# audio.net
KiCad netlist of a schematic drawn in Altium Designer
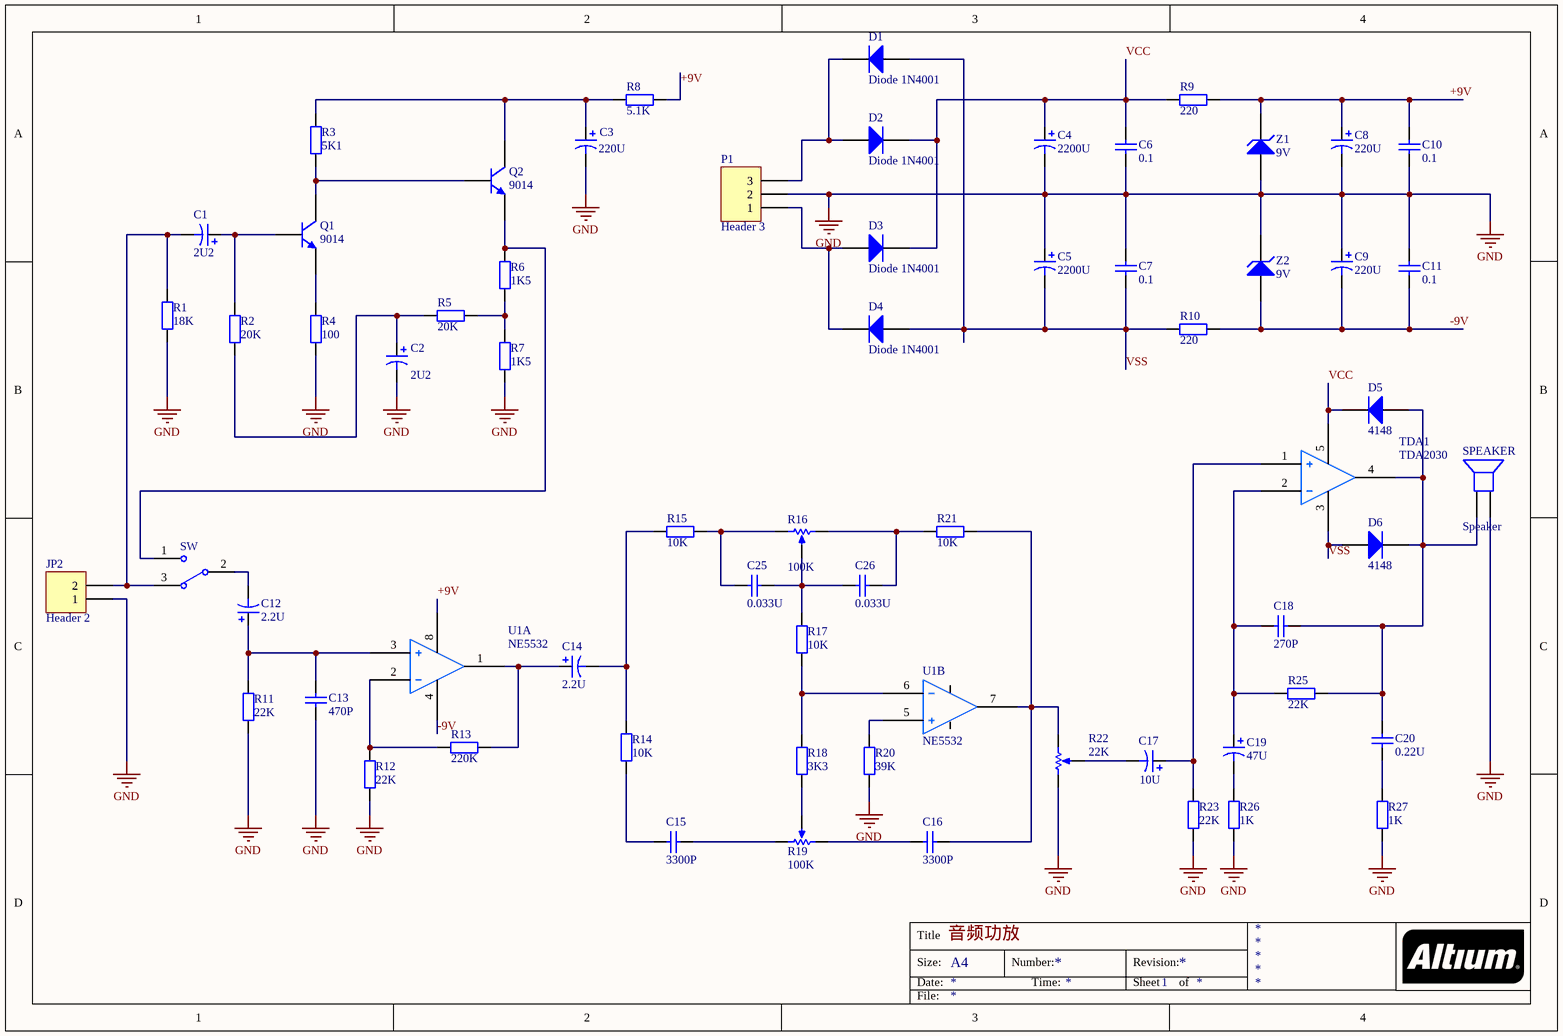
[diagram p0: audio.SchDoc]

(export (version "E")
  (design (tool "Eeschema 10.0.6"))
  (components
    (comp (ref "C1")
      (value "2U2")
      (footprint "CD0.2")
      (description "Polarized Capacitor (Radial)")
      (fields (field (name "PUBLISHER") "Altium Limited"))
      (libsource (lib "音频功放") (part "Cap Pol1"))
    )
    (comp (ref "C2")
      (value "2U2")
      (footprint "CD0.2")
      (description "Polarized Capacitor (Radial)")
      (fields (field (name "PUBLISHER") "Altium Limited"))
      (libsource (lib "音频功放") (part "Cap Pol1"))
    )
    (comp (ref "C3")
      (value "220U")
      (footprint "CD0.2")
      (description "Polarized Capacitor (Radial)")
      (fields (field (name "PUBLISHER") "Altium Limited"))
      (libsource (lib "音频功放") (part "Cap Pol1"))
    )
    (comp (ref "C4")
      (value "2200U")
      (footprint "CD0.2")
      (description "Polarized Capacitor (Radial)")
      (fields (field (name "PUBLISHER") "Altium Limited"))
      (libsource (lib "音频功放") (part "Cap Pol1"))
    )
    (comp (ref "C5")
      (value "2200U")
      (footprint "CD0.2")
      (description "Polarized Capacitor (Radial)")
      (fields (field (name "PUBLISHER") "Altium Limited"))
      (libsource (lib "音频功放") (part "Cap Pol1"))
    )
    (comp (ref "C6")
      (value "0.1")
      (footprint "C0.2A")
      (description "Capacitor")
      (fields (field (name "PUBLISHER") "Altium Limited"))
      (libsource (lib "音频功放") (part "Cap"))
    )
    (comp (ref "C7")
      (value "0.1")
      (footprint "C0.2A")
      (description "Capacitor")
      (fields (field (name "PUBLISHER") "Altium Limited"))
      (libsource (lib "音频功放") (part "Cap"))
    )
    (comp (ref "C8")
      (value "220U")
      (footprint "CD0.2")
      (description "Polarized Capacitor (Radial)")
      (fields (field (name "PUBLISHER") "Altium Limited"))
      (libsource (lib "音频功放") (part "Cap Pol1"))
    )
    (comp (ref "C9")
      (value "220U")
      (footprint "CD0.2")
      (description "Polarized Capacitor (Radial)")
      (fields (field (name "PUBLISHER") "Altium Limited"))
      (libsource (lib "音频功放") (part "Cap Pol1"))
    )
    (comp (ref "C10")
      (value "0.1")
      (footprint "C0.2A")
      (description "Capacitor")
      (fields (field (name "PUBLISHER") "Altium Limited"))
      (libsource (lib "音频功放") (part "Cap"))
    )
    (comp (ref "C11")
      (value "0.1")
      (footprint "C0.2A")
      (description "Capacitor")
      (fields (field (name "PUBLISHER") "Altium Limited"))
      (libsource (lib "音频功放") (part "Cap"))
    )
    (comp (ref "C12")
      (value "2.2U")
      (footprint "CD0.2")
      (description "Polarized Capacitor (Radial)")
      (fields (field (name "PUBLISHER") "Altium Limited"))
      (libsource (lib "音频功放") (part "Cap Pol1"))
    )
    (comp (ref "C13")
      (value "470P")
      (footprint "C0.2A")
      (description "Capacitor")
      (fields (field (name "PUBLISHER") "Altium Limited"))
      (libsource (lib "音频功放") (part "Cap"))
    )
    (comp (ref "C14")
      (value "2.2U")
      (footprint "CD0.2")
      (description "Polarized Capacitor (Radial)")
      (fields (field (name "PUBLISHER") "Altium Limited"))
      (libsource (lib "音频功放") (part "Cap Pol1"))
    )
    (comp (ref "C15")
      (value "3300P")
      (footprint "C0.2A")
      (description "Capacitor")
      (fields (field (name "PUBLISHER") "Altium Limited"))
      (libsource (lib "音频功放") (part "Cap"))
    )
    (comp (ref "C16")
      (value "3300P")
      (footprint "C0.2A")
      (description "Capacitor")
      (fields (field (name "PUBLISHER") "Altium Limited"))
      (libsource (lib "音频功放") (part "Cap"))
    )
    (comp (ref "C17")
      (value "10U")
      (footprint "CD0.2")
      (description "Polarized Capacitor (Radial)")
      (fields (field (name "PUBLISHER") "Altium Limited"))
      (libsource (lib "音频功放") (part "Cap Pol1"))
    )
    (comp (ref "C18")
      (value "270P")
      (footprint "C0.2A")
      (description "Capacitor")
      (fields (field (name "PUBLISHER") "Altium Limited"))
      (libsource (lib "音频功放") (part "Cap"))
    )
    (comp (ref "C19")
      (value "47U")
      (footprint "CD0.2")
      (description "Polarized Capacitor (Radial)")
      (fields (field (name "PUBLISHER") "Altium Limited"))
      (libsource (lib "音频功放") (part "Cap Pol1"))
    )
    (comp (ref "C20")
      (value "0.22U")
      (footprint "C0.2A")
      (description "Capacitor")
      (fields (field (name "PUBLISHER") "Altium Limited"))
      (libsource (lib "音频功放") (part "Cap"))
    )
    (comp (ref "C25")
      (value "0.033U")
      (footprint "C0.2A")
      (description "Capacitor")
      (fields (field (name "PUBLISHER") "Altium Limited"))
      (libsource (lib "音频功放") (part "Cap"))
    )
    (comp (ref "C26")
      (value "0.033U")
      (footprint "C0.2A")
      (description "Capacitor")
      (fields (field (name "PUBLISHER") "Altium Limited"))
      (libsource (lib "音频功放") (part "Cap"))
    )
    (comp (ref "D1")
      (value "Diode 1N4001")
      (footprint "DIODE0.4")
      (description "1 Amp General Purpose Rectifier")
      (fields (field (name "PUBLISHER") "Altium Limited"))
      (libsource (lib "音频功放") (part "Diode 1N4001"))
    )
    (comp (ref "D2")
      (value "Diode 1N4001")
      (footprint "DIODE0.4")
      (description "1 Amp General Purpose Rectifier")
      (fields (field (name "PUBLISHER") "Altium Limited"))
      (libsource (lib "音频功放") (part "Diode 1N4001"))
    )
    (comp (ref "D3")
      (value "Diode 1N4001")
      (footprint "DIODE0.4")
      (description "1 Amp General Purpose Rectifier")
      (fields (field (name "PUBLISHER") "Altium Limited"))
      (libsource (lib "音频功放") (part "Diode 1N4001"))
    )
    (comp (ref "D4")
      (value "Diode 1N4001")
      (footprint "DIODE0.4")
      (description "1 Amp General Purpose Rectifier")
      (fields (field (name "PUBLISHER") "Altium Limited"))
      (libsource (lib "音频功放") (part "Diode 1N4001"))
    )
    (comp (ref "D5")
      (value "4148")
      (footprint "DIODE0.4")
      (description "High Conductance Fast Diode")
      (fields (field (name "PUBLISHER") "Altium Limited"))
      (libsource (lib "音频功放") (part "Diode 1N4148"))
    )
    (comp (ref "D6")
      (value "4148")
      (footprint "DIODE0.4")
      (description "High Conductance Fast Diode")
      (fields (field (name "PUBLISHER") "Altium Limited"))
      (libsource (lib "音频功放") (part "Diode 1N4148"))
    )
    (comp (ref "JP2")
      (value "Header 2")
      (footprint "p2")
      (description "Header, 2-Pin")
      (fields (field (name "PUBLISHER") "Altium Limited"))
      (libsource (lib "音频功放") (part "Header 2"))
    )
    (comp (ref "P1")
      (value "Header 3")
      (footprint "p3")
      (description "Header, 3-Pin")
      (fields (field (name "PUBLISHER") "Altium Limited"))
      (libsource (lib "音频功放") (part "Header 3"))
    )
    (comp (ref "Q1")
      (value "9014")
      (footprint "TO-226-AA")
      (description "NPN General Purpose Amplifier")
      (fields (field (name "PUBLISHER") "Altium Limited"))
      (libsource (lib "音频功放") (part "2N3904"))
    )
    (comp (ref "Q2")
      (value "9014")
      (footprint "TO-226-AA")
      (description "NPN General Purpose Amplifier")
      (fields (field (name "PUBLISHER") "Altium Limited"))
      (libsource (lib "音频功放") (part "2N3904"))
    )
    (comp (ref "R1")
      (value "18K")
      (footprint "AXIAL-0.4")
      (description "Resistor")
      (fields (field (name "PUBLISHER") "Altium Limited"))
      (libsource (lib "音频功放") (part "Res2"))
    )
    (comp (ref "R2")
      (value "20K")
      (footprint "AXIAL-0.4")
      (description "Resistor")
      (fields (field (name "PUBLISHER") "Altium Limited"))
      (libsource (lib "音频功放") (part "Res2"))
    )
    (comp (ref "R3")
      (value "5K1")
      (footprint "AXIAL-0.4")
      (description "Resistor")
      (fields (field (name "PUBLISHER") "Altium Limited"))
      (libsource (lib "音频功放") (part "Res2"))
    )
    (comp (ref "R4")
      (value "100")
      (footprint "AXIAL-0.4")
      (description "Resistor")
      (fields (field (name "PUBLISHER") "Altium Limited"))
      (libsource (lib "音频功放") (part "Res2"))
    )
    (comp (ref "R5")
      (value "20K")
      (footprint "AXIAL-0.4")
      (description "Resistor")
      (fields (field (name "PUBLISHER") "Altium Limited"))
      (libsource (lib "") (part "Res2_1"))
    )
    (comp (ref "R6")
      (value "1K5")
      (footprint "AXIAL-0.4")
      (description "Resistor")
      (fields (field (name "PUBLISHER") "Altium Limited"))
      (libsource (lib "音频功放") (part "Res2"))
    )
    (comp (ref "R7")
      (value "1K5")
      (footprint "AXIAL-0.4")
      (description "Resistor")
      (fields (field (name "PUBLISHER") "Altium Limited"))
      (libsource (lib "音频功放") (part "Res2"))
    )
    (comp (ref "R8")
      (value "5.1K")
      (footprint "AXIAL-0.4")
      (description "Resistor")
      (fields (field (name "PUBLISHER") "Altium Limited"))
      (libsource (lib "") (part "Res2_1"))
    )
    (comp (ref "R9")
      (value "220")
      (footprint "AXIAL-0.4")
      (description "Resistor")
      (fields (field (name "PUBLISHER") "Altium Limited"))
      (libsource (lib "") (part "Res2_1"))
    )
    (comp (ref "R10")
      (value "220")
      (footprint "AXIAL-0.4")
      (description "Resistor")
      (fields (field (name "PUBLISHER") "Altium Limited"))
      (libsource (lib "") (part "Res2_1"))
    )
    (comp (ref "R11")
      (value "22K")
      (footprint "AXIAL-0.4")
      (description "Resistor")
      (fields (field (name "PUBLISHER") "Altium Limited"))
      (libsource (lib "音频功放") (part "Res2"))
    )
    (comp (ref "R12")
      (value "22K")
      (footprint "AXIAL-0.4")
      (description "Resistor")
      (fields (field (name "PUBLISHER") "Altium Limited"))
      (libsource (lib "音频功放") (part "Res2"))
    )
    (comp (ref "R13")
      (value "220K")
      (footprint "AXIAL-0.4")
      (description "Resistor")
      (fields (field (name "PUBLISHER") "Altium Limited"))
      (libsource (lib "") (part "Res2_1"))
    )
    (comp (ref "R14")
      (value "10K")
      (footprint "AXIAL-0.4")
      (description "Resistor")
      (fields (field (name "PUBLISHER") "Altium Limited"))
      (libsource (lib "音频功放") (part "Res2"))
    )
    (comp (ref "R15")
      (value "10K")
      (footprint "AXIAL-0.4")
      (description "Resistor")
      (fields (field (name "PUBLISHER") "Altium Limited"))
      (libsource (lib "") (part "Res2_1"))
    )
    (comp (ref "R16")
      (value "100K")
      (footprint "LK01")
      (description "Potentiometer")
      (fields (field (name "PUBLISHER") "Altium Limited"))
      (libsource (lib "音频功放") (part "RPot"))
    )
    (comp (ref "R17")
      (value "10K")
      (footprint "AXIAL-0.4")
      (description "Resistor")
      (fields (field (name "PUBLISHER") "Altium Limited"))
      (libsource (lib "音频功放") (part "Res2"))
    )
    (comp (ref "R18")
      (value "3K3")
      (footprint "AXIAL-0.4")
      (description "Resistor")
      (fields (field (name "PUBLISHER") "Altium Limited"))
      (libsource (lib "音频功放") (part "Res2"))
    )
    (comp (ref "R19")
      (value "100K")
      (footprint "LK01")
      (description "Potentiometer")
      (fields (field (name "PUBLISHER") "Altium Limited"))
      (libsource (lib "音频功放") (part "RPot"))
    )
    (comp (ref "R20")
      (value "39K")
      (footprint "AXIAL-0.4")
      (description "Resistor")
      (fields (field (name "PUBLISHER") "Altium Limited"))
      (libsource (lib "音频功放") (part "Res2"))
    )
    (comp (ref "R21")
      (value "10K")
      (footprint "AXIAL-0.4")
      (description "Resistor")
      (fields (field (name "PUBLISHER") "Altium Limited"))
      (libsource (lib "") (part "Res2_1"))
    )
    (comp (ref "R22")
      (value "22K")
      (footprint "LK01")
      (description "Potentiometer")
      (fields (field (name "PUBLISHER") "Altium Limited"))
      (libsource (lib "音频功放") (part "RPot"))
    )
    (comp (ref "R23")
      (value "22K")
      (footprint "AXIAL-0.4")
      (description "Resistor")
      (fields (field (name "PUBLISHER") "Altium Limited"))
      (libsource (lib "音频功放") (part "Res2"))
    )
    (comp (ref "R25")
      (value "22K")
      (footprint "AXIAL-0.4")
      (description "Resistor")
      (fields (field (name "PUBLISHER") "Altium Limited"))
      (libsource (lib "") (part "Res2_1"))
    )
    (comp (ref "R26")
      (value "1K")
      (footprint "AXIAL-0.4")
      (description "Resistor")
      (fields (field (name "PUBLISHER") "Altium Limited"))
      (libsource (lib "音频功放") (part "Res2"))
    )
    (comp (ref "R27")
      (value "1K")
      (footprint "AXIAL-0.4")
      (description "Resistor")
      (fields (field (name "PUBLISHER") "Altium Limited"))
      (libsource (lib "音频功放") (part "Res2"))
    )
    (comp (ref "SPEAKER")
      (value "Speaker")
      (footprint "p2")
      (description "Loudspeaker")
      (fields (field (name "PUBLISHER") "Altium Limited"))
      (libsource (lib "音频功放") (part "Speaker"))
    )
    (comp (ref "SW")
      (value "SW-SPDT")
      (footprint "SW")
      (description "SPDT Subminiature Toggle Switch, Right Angle Mounting, Vertical Actuation")
      (fields (field (name "PUBLISHER") "Altium Limited"))
      (libsource (lib "音频功放") (part "SW-SPDT"))
    )
    (comp (ref "TDA1") (value "TDA2030") (footprint "7805E") (libsource (lib "音频功放") (part "TDA2030")))
    (comp (ref "U1") (value "NE5532") (footprint "DIP8") (libsource (lib "音频功放") (part "NE5532")))
    (comp (ref "Z1")
      (value "9V")
      (footprint "DIODE0.4")
      (description "Zener Diode")
      (fields (field (name "PUBLISHER") "Altium Limited"))
      (libsource (lib "音频功放") (part "D Zener"))
    )
    (comp (ref "Z2")
      (value "9V")
      (footprint "DIODE0.4")
      (description "Zener Diode")
      (fields (field (name "PUBLISHER") "Altium Limited"))
      (libsource (lib "音频功放") (part "D Zener"))
    )
  )
  (nets
    (net (code "1") (name "/+9V") (class "Default")
      (node (ref "C10") (pin "1") (pinfunction "1_1") (pintype "passive"))
      (node (ref "C8") (pin "1") (pinfunction "1_1") (pintype "passive"))
      (node (ref "R8") (pin "2") (pinfunction "2_2") (pintype "passive"))
      (node (ref "R9") (pin "2") (pinfunction "2_2") (pintype "passive"))
      (node (ref "U1") (pin "8") (pintype "passive"))
      (node (ref "Z1") (pin "2") (pinfunction "K_2") (pintype "passive"))
    )
    (net (code "2") (name "/-9V") (class "Default")
      (node (ref "C11") (pin "2") (pinfunction "2_2") (pintype "passive"))
      (node (ref "C9") (pin "2") (pinfunction "2_2") (pintype "passive"))
      (node (ref "R10") (pin "2") (pinfunction "2_2") (pintype "passive"))
      (node (ref "U1") (pin "4") (pintype "passive"))
      (node (ref "Z2") (pin "1") (pinfunction "A_1") (pintype "passive"))
    )
    (net (code "3") (name "/VCC") (class "Default")
      (node (ref "C4") (pin "1") (pinfunction "1_1") (pintype "passive"))
      (node (ref "C6") (pin "2") (pinfunction "2_2") (pintype "passive"))
      (node (ref "D2") (pin "2") (pinfunction "K_2") (pintype "passive"))
      (node (ref "D3") (pin "2") (pinfunction "K_2") (pintype "passive"))
      (node (ref "D5") (pin "2") (pinfunction "K_2") (pintype "passive"))
      (node (ref "R9") (pin "1") (pinfunction "1_1") (pintype "passive"))
      (node (ref "TDA1") (pin "5") (pintype "passive"))
    )
    (net (code "4") (name "/VSS") (class "Default")
      (node (ref "C5") (pin "2") (pinfunction "2_2") (pintype "passive"))
      (node (ref "C7") (pin "1") (pinfunction "1_1") (pintype "passive"))
      (node (ref "D1") (pin "1") (pinfunction "A_1") (pintype "passive"))
      (node (ref "D4") (pin "1") (pinfunction "A_1") (pintype "passive"))
      (node (ref "D6") (pin "1") (pinfunction "A_1") (pintype "passive"))
      (node (ref "R10") (pin "1") (pinfunction "1_1") (pintype "passive"))
      (node (ref "TDA1") (pin "3") (pintype "passive"))
    )
    (net (code "5") (name "GND") (class "Default")
      (node (ref "C10") (pin "2") (pinfunction "2_2") (pintype "passive"))
      (node (ref "C11") (pin "1") (pinfunction "1_1") (pintype "passive"))
      (node (ref "C13") (pin "1") (pinfunction "1_1") (pintype "passive"))
      (node (ref "C2") (pin "2") (pinfunction "2_2") (pintype "passive"))
      (node (ref "C3") (pin "2") (pinfunction "2_2") (pintype "passive"))
      (node (ref "C4") (pin "2") (pinfunction "2_2") (pintype "passive"))
      (node (ref "C5") (pin "1") (pinfunction "1_1") (pintype "passive"))
      (node (ref "C6") (pin "1") (pinfunction "1_1") (pintype "passive"))
      (node (ref "C7") (pin "2") (pinfunction "2_2") (pintype "passive"))
      (node (ref "C8") (pin "2") (pinfunction "2_2") (pintype "passive"))
      (node (ref "C9") (pin "1") (pinfunction "1_1") (pintype "passive"))
      (node (ref "JP2") (pin "1") (pinfunction "1_1") (pintype "passive"))
      (node (ref "P1") (pin "2") (pinfunction "2_2") (pintype "passive"))
      (node (ref "R1") (pin "1") (pinfunction "1_1") (pintype "passive"))
      (node (ref "R11") (pin "1") (pinfunction "1_1") (pintype "passive"))
      (node (ref "R12") (pin "1") (pinfunction "1_1") (pintype "passive"))
      (node (ref "R20") (pin "1") (pinfunction "1_1") (pintype "passive"))
      (node (ref "R22") (pin "1") (pinfunction "TOP_1") (pintype "passive"))
      (node (ref "R23") (pin "1") (pinfunction "1_1") (pintype "passive"))
      (node (ref "R26") (pin "1") (pinfunction "1_1") (pintype "passive"))
      (node (ref "R27") (pin "1") (pinfunction "1_1") (pintype "passive"))
      (node (ref "R4") (pin "1") (pinfunction "1_1") (pintype "passive"))
      (node (ref "R7") (pin "1") (pinfunction "1_1") (pintype "passive"))
      (node (ref "SPEAKER") (pin "2") (pinfunction "2_2") (pintype "passive"))
      (node (ref "Z1") (pin "1") (pinfunction "A_1") (pintype "passive"))
      (node (ref "Z2") (pin "2") (pinfunction "K_2") (pintype "passive"))
    )
    (net (code "6") (name "Net-(C1-Pad2)") (class "Default")
      (node (ref "C1") (pin "2") (pinfunction "2_2") (pintype "passive"))
      (node (ref "JP2") (pin "2") (pinfunction "2_2") (pintype "passive"))
      (node (ref "R1") (pin "2") (pinfunction "2_2") (pintype "passive"))
      (node (ref "SW") (pin "3") (pinfunction "3_3") (pintype "passive"))
    )
    (net (code "7") (name "Net-(C2-Pad1)") (class "Default")
      (node (ref "C2") (pin "1") (pinfunction "1_1") (pintype "passive"))
      (node (ref "R2") (pin "1") (pinfunction "1_1") (pintype "passive"))
      (node (ref "R5") (pin "1") (pinfunction "1_1") (pintype "passive"))
    )
    (net (code "8") (name "Net-(C12-Pad1)") (class "Default")
      (node (ref "C12") (pin "1") (pinfunction "1_1") (pintype "passive"))
      (node (ref "C13") (pin "2") (pinfunction "2_2") (pintype "passive"))
      (node (ref "R11") (pin "2") (pinfunction "2_2") (pintype "passive"))
      (node (ref "U1") (pin "3") (pintype "passive"))
    )
    (net (code "9") (name "Net-(C12-Pad2)") (class "Default")
      (node (ref "C12") (pin "2") (pinfunction "2_2") (pintype "passive"))
      (node (ref "SW") (pin "2") (pinfunction "2_2") (pintype "passive"))
    )
    (net (code "10") (name "Net-(C14-Pad1)") (class "Default")
      (node (ref "C14") (pin "1") (pinfunction "1_1") (pintype "passive"))
      (node (ref "R13") (pin "2") (pinfunction "2_2") (pintype "passive"))
      (node (ref "U1") (pin "1") (pintype "passive"))
    )
    (net (code "11") (name "Net-(C14-Pad2)") (class "Default")
      (node (ref "C14") (pin "2") (pinfunction "2_2") (pintype "passive"))
      (node (ref "R14") (pin "2") (pinfunction "2_2") (pintype "passive"))
      (node (ref "R15") (pin "1") (pinfunction "1_1") (pintype "passive"))
    )
    (net (code "12") (name "Net-(C15-Pad1)") (class "Default")
      (node (ref "C15") (pin "1") (pinfunction "1_1") (pintype "passive"))
      (node (ref "R14") (pin "1") (pinfunction "1_1") (pintype "passive"))
    )
    (net (code "13") (name "Net-(C17-Pad1)") (class "Default")
      (node (ref "C17") (pin "1") (pinfunction "1_1") (pintype "passive"))
      (node (ref "R23") (pin "2") (pinfunction "2_2") (pintype "passive"))
      (node (ref "TDA1") (pin "1") (pintype "passive"))
    )
    (net (code "14") (name "Net-(C18-Pad1)") (class "Default")
      (node (ref "C18") (pin "1") (pinfunction "1_1") (pintype "passive"))
      (node (ref "C19") (pin "1") (pinfunction "1_1") (pintype "passive"))
      (node (ref "R25") (pin "1") (pinfunction "1_1") (pintype "passive"))
      (node (ref "TDA1") (pin "2") (pintype "passive"))
    )
    (net (code "15") (name "Net-(C19-Pad2)") (class "Default")
      (node (ref "C19") (pin "2") (pinfunction "2_2") (pintype "passive"))
      (node (ref "R26") (pin "2") (pinfunction "2_2") (pintype "passive"))
    )
    (net (code "16") (name "Net-(C20-Pad1)") (class "Default")
      (node (ref "C20") (pin "1") (pinfunction "1_1") (pintype "passive"))
      (node (ref "R27") (pin "2") (pinfunction "2_2") (pintype "passive"))
    )
    (net (code "17") (name "Net-(D1-K)") (class "Default")
      (node (ref "D1") (pin "2") (pinfunction "K_2") (pintype "passive"))
      (node (ref "D2") (pin "1") (pinfunction "A_1") (pintype "passive"))
      (node (ref "P1") (pin "3") (pinfunction "3_3") (pintype "passive"))
    )
    (net (code "18") (name "Net-(D3-A)") (class "Default")
      (node (ref "D3") (pin "1") (pinfunction "A_1") (pintype "passive"))
      (node (ref "D4") (pin "2") (pinfunction "K_2") (pintype "passive"))
      (node (ref "P1") (pin "1") (pinfunction "1_1") (pintype "passive"))
    )
    (net (code "19") (name "Net-(D5-A)") (class "Default")
      (node (ref "C18") (pin "2") (pinfunction "2_2") (pintype "passive"))
      (node (ref "C20") (pin "2") (pinfunction "2_2") (pintype "passive"))
      (node (ref "D5") (pin "1") (pinfunction "A_1") (pintype "passive"))
      (node (ref "D6") (pin "2") (pinfunction "K_2") (pintype "passive"))
      (node (ref "R25") (pin "2") (pinfunction "2_2") (pintype "passive"))
      (node (ref "SPEAKER") (pin "1") (pinfunction "1_1") (pintype "passive"))
      (node (ref "TDA1") (pin "4") (pintype "passive"))
    )
    (net (code "20") (name "Net-(Q1-B)") (class "Default")
      (node (ref "C1") (pin "1") (pinfunction "1_1") (pintype "passive"))
      (node (ref "Q1") (pin "2") (pinfunction "B_2") (pintype "passive"))
      (node (ref "R2") (pin "2") (pinfunction "2_2") (pintype "passive"))
    )
    (net (code "21") (name "Net-(Q1-C)") (class "Default")
      (node (ref "Q1") (pin "3") (pinfunction "C_3") (pintype "passive"))
      (node (ref "Q2") (pin "2") (pinfunction "B_2") (pintype "passive"))
      (node (ref "R3") (pin "1") (pinfunction "1_1") (pintype "passive"))
    )
    (net (code "22") (name "Net-(Q1-E)") (class "Default")
      (node (ref "Q1") (pin "1") (pinfunction "E_1") (pintype "passive"))
      (node (ref "R4") (pin "2") (pinfunction "2_2") (pintype "passive"))
    )
    (net (code "23") (name "Net-(Q2-C)") (class "Default")
      (node (ref "C3") (pin "1") (pinfunction "1_1") (pintype "passive"))
      (node (ref "Q2") (pin "3") (pinfunction "C_3") (pintype "passive"))
      (node (ref "R3") (pin "2") (pinfunction "2_2") (pintype "passive"))
      (node (ref "R8") (pin "1") (pinfunction "1_1") (pintype "passive"))
    )
    (net (code "24") (name "Net-(Q2-E)") (class "Default")
      (node (ref "Q2") (pin "1") (pinfunction "E_1") (pintype "passive"))
      (node (ref "R6") (pin "2") (pinfunction "2_2") (pintype "passive"))
      (node (ref "SW") (pin "1") (pinfunction "1_1") (pintype "passive"))
    )
    (net (code "25") (name "Net-(R5-Pad2)") (class "Default")
      (node (ref "R5") (pin "2") (pinfunction "2_2") (pintype "passive"))
      (node (ref "R6") (pin "1") (pinfunction "1_1") (pintype "passive"))
      (node (ref "R7") (pin "2") (pinfunction "2_2") (pintype "passive"))
    )
    (net (code "26") (name "Net-(R12-Pad2)") (class "Default")
      (node (ref "R12") (pin "2") (pinfunction "2_2") (pintype "passive"))
      (node (ref "R13") (pin "1") (pinfunction "1_1") (pintype "passive"))
      (node (ref "U1") (pin "2") (pintype "passive"))
    )
    (net (code "27") (name "Net-(R16-BOT)") (class "Default")
      (node (ref "C26") (pin "2") (pinfunction "2_2") (pintype "passive"))
      (node (ref "R16") (pin "2") (pinfunction "BOT_2") (pintype "passive"))
      (node (ref "R21") (pin "1") (pinfunction "1_1") (pintype "passive"))
    )
    (net (code "28") (name "Net-(R16-TAP)") (class "Default")
      (node (ref "C25") (pin "2") (pinfunction "2_2") (pintype "passive"))
      (node (ref "C26") (pin "1") (pinfunction "1_1") (pintype "passive"))
      (node (ref "R16") (pin "3") (pinfunction "TAP_3") (pintype "passive"))
      (node (ref "R17") (pin "2") (pinfunction "2_2") (pintype "passive"))
    )
    (net (code "29") (name "Net-(R16-TOP)") (class "Default")
      (node (ref "C25") (pin "1") (pinfunction "1_1") (pintype "passive"))
      (node (ref "R15") (pin "2") (pinfunction "2_2") (pintype "passive"))
      (node (ref "R16") (pin "1") (pinfunction "TOP_1") (pintype "passive"))
    )
    (net (code "30") (name "Net-(R17-Pad1)") (class "Default")
      (node (ref "R17") (pin "1") (pinfunction "1_1") (pintype "passive"))
      (node (ref "R18") (pin "2") (pinfunction "2_2") (pintype "passive"))
      (node (ref "U1") (pin "6") (pintype "passive"))
    )
    (net (code "31") (name "Net-(R19-BOT)") (class "Default")
      (node (ref "C15") (pin "2") (pinfunction "2_2") (pintype "passive"))
      (node (ref "R19") (pin "2") (pinfunction "BOT_2") (pintype "passive"))
    )
    (net (code "32") (name "Net-(R19-TAP)") (class "Default")
      (node (ref "R18") (pin "1") (pinfunction "1_1") (pintype "passive"))
      (node (ref "R19") (pin "3") (pinfunction "TAP_3") (pintype "passive"))
    )
    (net (code "33") (name "Net-(R19-TOP)") (class "Default")
      (node (ref "C16") (pin "1") (pinfunction "1_1") (pintype "passive"))
      (node (ref "R19") (pin "1") (pinfunction "TOP_1") (pintype "passive"))
    )
    (net (code "34") (name "Net-(R20-Pad2)") (class "Default")
      (node (ref "R20") (pin "2") (pinfunction "2_2") (pintype "passive"))
      (node (ref "U1") (pin "5") (pintype "passive"))
    )
    (net (code "35") (name "Net-(R22-BOT)") (class "Default")
      (node (ref "C16") (pin "2") (pinfunction "2_2") (pintype "passive"))
      (node (ref "R21") (pin "2") (pinfunction "2_2") (pintype "passive"))
      (node (ref "R22") (pin "2") (pinfunction "BOT_2") (pintype "passive"))
      (node (ref "U1") (pin "7") (pintype "passive"))
    )
    (net (code "36") (name "Net-(R22-TAP)") (class "Default")
      (node (ref "C17") (pin "2") (pinfunction "2_2") (pintype "passive"))
      (node (ref "R22") (pin "3") (pinfunction "TAP_3") (pintype "passive"))
    )
  )
)
